# ssd_blinky_eagle.net
KiCad netlist of a schematic drawn in EAGLE
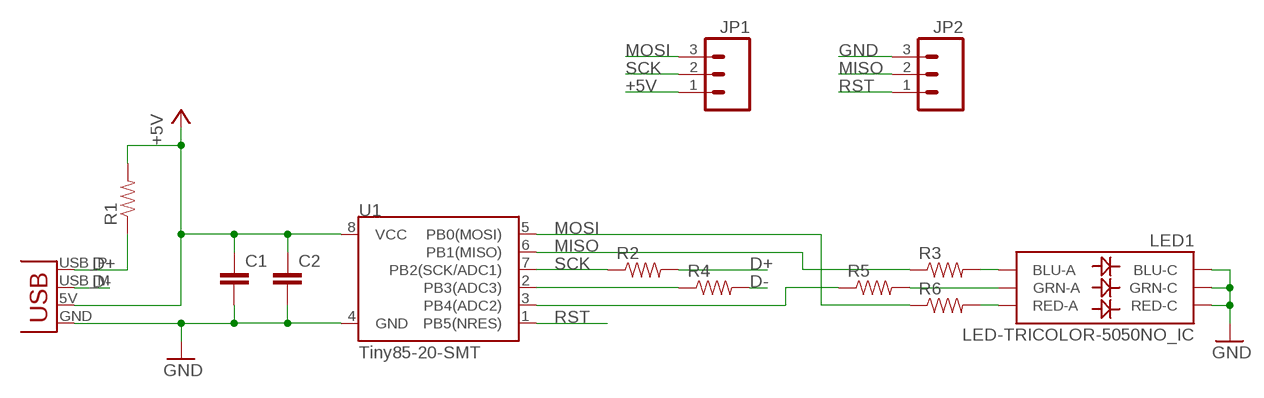
[diagram p0: schematic, sheet 1]

(export (version "E")
  (design (tool "Eeschema 10.0.6"))
  (components
    (comp (ref "C1")
      (value "CAP1206")
      (footprint "eagle-import:1206")
      (libsource (lib "eagle-import") (part "CAP1206"))
    )
    (comp (ref "C2")
      (value "CAP1206")
      (footprint "eagle-import:1206")
      (libsource (lib "eagle-import") (part "CAP1206"))
    )
    (comp (ref "JP1")
      (value "M03SMD_RA_MALE")
      (footprint "eagle-import:1X03_SMD_RA_MALE")
      (libsource (lib "eagle-import") (part "M03SMD_RA_MALE"))
    )
    (comp (ref "JP2")
      (value "M03SMD_RA_MALE")
      (footprint "eagle-import:1X03_SMD_RA_MALE")
      (libsource (lib "eagle-import") (part "M03SMD_RA_MALE"))
    )
    (comp (ref "JP3")
      (value "USBPCB")
      (footprint "eagle-import:USB-A-PCB")
      (libsource (lib "eagle-import") (part "USBPCB"))
    )
    (comp (ref "LED1")
      (value "LED-TRICOLOR-5050NO_IC")
      (footprint "eagle-import:LED-TRICOLOR-5050")
      (libsource (lib "eagle-import") (part "LED-TRICOLOR-5050NO_IC"))
    )
    (comp (ref "R1")
      (value "RESISTOR1206")
      (footprint "eagle-import:1206")
      (libsource (lib "eagle-import") (part "RESISTOR1206"))
    )
    (comp (ref "R2")
      (value "RESISTOR1206")
      (footprint "eagle-import:1206")
      (libsource (lib "eagle-import") (part "RESISTOR1206"))
    )
    (comp (ref "R3")
      (value "RESISTOR1206")
      (footprint "eagle-import:1206")
      (libsource (lib "eagle-import") (part "RESISTOR1206"))
    )
    (comp (ref "R4")
      (value "RESISTOR1206")
      (footprint "eagle-import:1206")
      (libsource (lib "eagle-import") (part "RESISTOR1206"))
    )
    (comp (ref "R5")
      (value "RESISTOR1206")
      (footprint "eagle-import:1206")
      (libsource (lib "eagle-import") (part "RESISTOR1206"))
    )
    (comp (ref "R6")
      (value "RESISTOR1206")
      (footprint "eagle-import:1206")
      (libsource (lib "eagle-import") (part "RESISTOR1206"))
    )
    (comp (ref "U1")
      (value "Tiny85-20-SMT")
      (footprint "eagle-import:SO08-EIAJ")
      (libsource (lib "eagle-import") (part "ATTINY45TINY85-20-SMT"))
    )
  )
  (nets
    (net (code "1") (name "+5V") (class "Default")
      (node (ref "C1") (pin "1") (pinfunction "1_1") (pintype "passive"))
      (node (ref "C2") (pin "1") (pinfunction "1_1") (pintype "passive"))
      (node (ref "JP1") (pin "1") (pinfunction "1_1") (pintype "passive"))
      (node (ref "JP3") (pin "5V") (pinfunction "VBUS_5V") (pintype "bidirectional"))
      (node (ref "R1") (pin "2") (pinfunction "2_2") (pintype "passive"))
      (node (ref "U1") (pin "8") (pinfunction "VCC_8") (pintype "bidirectional"))
    )
    (net (code "2") (name "/D+") (class "Default")
      (node (ref "JP3") (pin "USB_P") (pinfunction "D+_USB_P") (pintype "bidirectional"))
      (node (ref "R1") (pin "1") (pinfunction "1_1") (pintype "passive"))
      (node (ref "R2") (pin "2") (pinfunction "2_2") (pintype "passive"))
    )
    (net (code "3") (name "/D-") (class "Default")
      (node (ref "JP3") (pin "USB_M") (pinfunction "D-_USB_M") (pintype "bidirectional"))
      (node (ref "R4") (pin "2") (pinfunction "2_2") (pintype "passive"))
    )
    (net (code "4") (name "/MISO") (class "Default")
      (node (ref "JP2") (pin "2") (pinfunction "2_2") (pintype "passive"))
      (node (ref "R5") (pin "1") (pinfunction "1_1") (pintype "passive"))
      (node (ref "U1") (pin "3") (pinfunction "PB4(ADC2)_3") (pintype "bidirectional"))
    )
    (net (code "5") (name "/MOSI") (class "Default")
      (node (ref "JP1") (pin "3") (pinfunction "3_3") (pintype "passive"))
      (node (ref "R6") (pin "1") (pinfunction "1_1") (pintype "passive"))
      (node (ref "U1") (pin "5") (pinfunction "PB0(MOSI)_5") (pintype "bidirectional"))
    )
    (net (code "6") (name "/RST") (class "Default")
      (node (ref "JP2") (pin "1") (pinfunction "1_1") (pintype "passive"))
      (node (ref "U1") (pin "1") (pinfunction "PB5(NRES)_1") (pintype "bidirectional"))
    )
    (net (code "7") (name "/SCK") (class "Default")
      (node (ref "JP1") (pin "2") (pinfunction "2_2") (pintype "passive"))
      (node (ref "R2") (pin "1") (pinfunction "1_1") (pintype "passive"))
      (node (ref "U1") (pin "7") (pinfunction "PB2(SCK/ADC1)_7") (pintype "bidirectional"))
    )
    (net (code "8") (name "GND") (class "Default")
      (node (ref "C1") (pin "2") (pinfunction "2_2") (pintype "passive"))
      (node (ref "C2") (pin "2") (pinfunction "2_2") (pintype "passive"))
      (node (ref "JP2") (pin "3") (pinfunction "3_3") (pintype "passive"))
      (node (ref "JP3") (pin "GND") (pinfunction "GND_GND") (pintype "bidirectional"))
      (node (ref "LED1") (pin "4") (pinfunction "BLU-C_4") (pintype "bidirectional"))
      (node (ref "LED1") (pin "5") (pinfunction "RED-C_5") (pintype "bidirectional"))
      (node (ref "LED1") (pin "6") (pinfunction "GRN-C_6") (pintype "bidirectional"))
      (node (ref "U1") (pin "4") (pinfunction "GND_4") (pintype "bidirectional"))
    )
    (net (code "9") (name "Net-(LED1-BLU-A)") (class "Default")
      (node (ref "LED1") (pin "3") (pinfunction "BLU-A_3") (pintype "bidirectional"))
      (node (ref "R3") (pin "2") (pinfunction "2_2") (pintype "passive"))
    )
    (net (code "10") (name "Net-(LED1-GRN-A)") (class "Default")
      (node (ref "LED1") (pin "1") (pinfunction "GRN-A_1") (pintype "bidirectional"))
      (node (ref "R5") (pin "2") (pinfunction "2_2") (pintype "passive"))
    )
    (net (code "11") (name "Net-(LED1-RED-A)") (class "Default")
      (node (ref "LED1") (pin "2") (pinfunction "RED-A_2") (pintype "bidirectional"))
      (node (ref "R6") (pin "2") (pinfunction "2_2") (pintype "passive"))
    )
    (net (code "12") (name "Net-(U1-PB1(MISO))") (class "Default")
      (node (ref "R3") (pin "1") (pinfunction "1_1") (pintype "passive"))
      (node (ref "U1") (pin "6") (pinfunction "PB1(MISO)_6") (pintype "bidirectional"))
    )
    (net (code "13") (name "Net-(U1-PB3(ADC3))") (class "Default")
      (node (ref "R4") (pin "1") (pinfunction "1_1") (pintype "passive"))
      (node (ref "U1") (pin "2") (pinfunction "PB3(ADC3)_2") (pintype "bidirectional"))
    )
  )
)
